# Power.net
KiCad netlist of a schematic drawn in Altium Designer
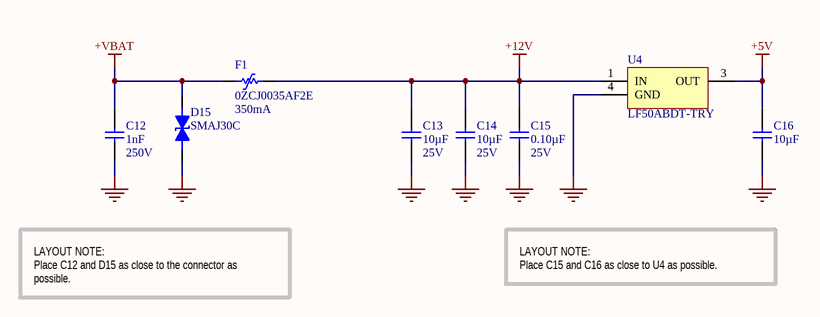
[diagram p0: Power.SchDoc]

(export (version "E")
  (design (tool "Eeschema 10.0.6"))
  (components
    (comp (ref "C12")
      (value "1nF")
      (footprint "CAP-0805-M")
      (fields
        (field (name "PART NUMBER") "CC0805KRX7RYBB102")
        (field (name "TOLERANCE") "±10%")
        (field (name "VOLTAGE") "250V")
        (field (name "MANUFACTURER") "Yageo")
      )
      (libsource (lib "Capacitors") (part "Capacitor"))
    )
    (comp (ref "C13")
      (value "10µF")
      (footprint "CAP-1206-M")
      (fields
        (field (name "PART NUMBER") "CC1206KKX7R8BB106")
        (field (name "TOLERANCE") "±10%")
        (field (name "VOLTAGE") "25V")
        (field (name "MANUFACTURER") "Yageo")
      )
      (libsource (lib "Capacitors") (part "Capacitor"))
    )
    (comp (ref "C14")
      (value "10µF")
      (footprint "CAP-1206-M")
      (fields
        (field (name "PART NUMBER") "CC1206KKX7R8BB106")
        (field (name "TOLERANCE") "±10%")
        (field (name "VOLTAGE") "25V")
        (field (name "MANUFACTURER") "Yageo")
      )
      (libsource (lib "Capacitors") (part "Capacitor"))
    )
    (comp (ref "C15")
      (value "0.10µF")
      (footprint "CAP-0402-M")
      (fields
        (field (name "PART NUMBER") "CC0402KRX7R8BB104")
        (field (name "TOLERANCE") "±10%")
        (field (name "VOLTAGE") "25V")
        (field (name "MANUFACTURER") "Yageo")
      )
      (libsource (lib "Capacitors") (part "Capacitor"))
    )
    (comp (ref "C16")
      (value "10µF")
      (footprint "CAP-0805-M")
      (fields
        (field (name "PART NUMBER") "CC0805KKX7R5BB106")
        (field (name "TOLERANCE") "±10%")
        (field (name "VOLTAGE") "6.3V")
      )
      (libsource (lib "Capacitors") (part "Capacitor"))
    )
    (comp (ref "D15")
      (value "SMAJ30C")
      (footprint "SON127P500X135-2N")
      (libsource (lib "CANio") (part "SMAJ30C"))
    )
    (comp (ref "F1")
      (value "0ZCJ0035AF2E")
      (footprint "0ZCJ-1206-0.9")
      (fields (field (name "ALTIUM_VALUE") "350mA"))
      (libsource (lib "CANio") (part "0ZCJ0035AF2E"))
    )
    (comp (ref "U4")
      (value "LF50ABDT-TRY")
      (footprint "DPAK228P972X240-3N")
      (libsource (lib "CANwheel") (part "LF50ABDT-TRY"))
    )
  )
  (nets
    (net (code "1") (name "+5V") (class "Default")
      (node (ref "C16") (pin "1") (pinfunction "1_1") (pintype "passive"))
      (node (ref "U4") (pin "3") (pinfunction "OUT_3") (pintype "power_in"))
    )
    (net (code "2") (name "+12V") (class "Default")
      (node (ref "C13") (pin "2") (pinfunction "2_2") (pintype "passive"))
      (node (ref "C14") (pin "2") (pinfunction "2_2") (pintype "passive"))
      (node (ref "C15") (pin "2") (pinfunction "2_2") (pintype "passive"))
      (node (ref "F1") (pin "2") (pinfunction "2_2") (pintype "passive"))
      (node (ref "U4") (pin "1") (pinfunction "IN_1") (pintype "power_in"))
    )
    (net (code "3") (name "+VBAT") (class "Default")
      (node (ref "C12") (pin "1") (pinfunction "1_1") (pintype "passive"))
      (node (ref "D15") (pin "1") (pinfunction "1_1") (pintype "passive"))
      (node (ref "F1") (pin "1") (pinfunction "1_1") (pintype "passive"))
    )
    (net (code "4") (name "GND") (class "Default")
      (node (ref "C12") (pin "2") (pinfunction "2_2") (pintype "passive"))
      (node (ref "C13") (pin "1") (pinfunction "1_1") (pintype "passive"))
      (node (ref "C14") (pin "1") (pinfunction "1_1") (pintype "passive"))
      (node (ref "C15") (pin "1") (pinfunction "1_1") (pintype "passive"))
      (node (ref "C16") (pin "2") (pinfunction "2_2") (pintype "passive"))
      (node (ref "D15") (pin "2") (pinfunction "2_2") (pintype "passive"))
      (node (ref "U4") (pin "4") (pinfunction "GND_4") (pintype "passive"))
    )
  )
)
